# tin_of_fets.net
KiCad netlist of a schematic drawn in EAGLE
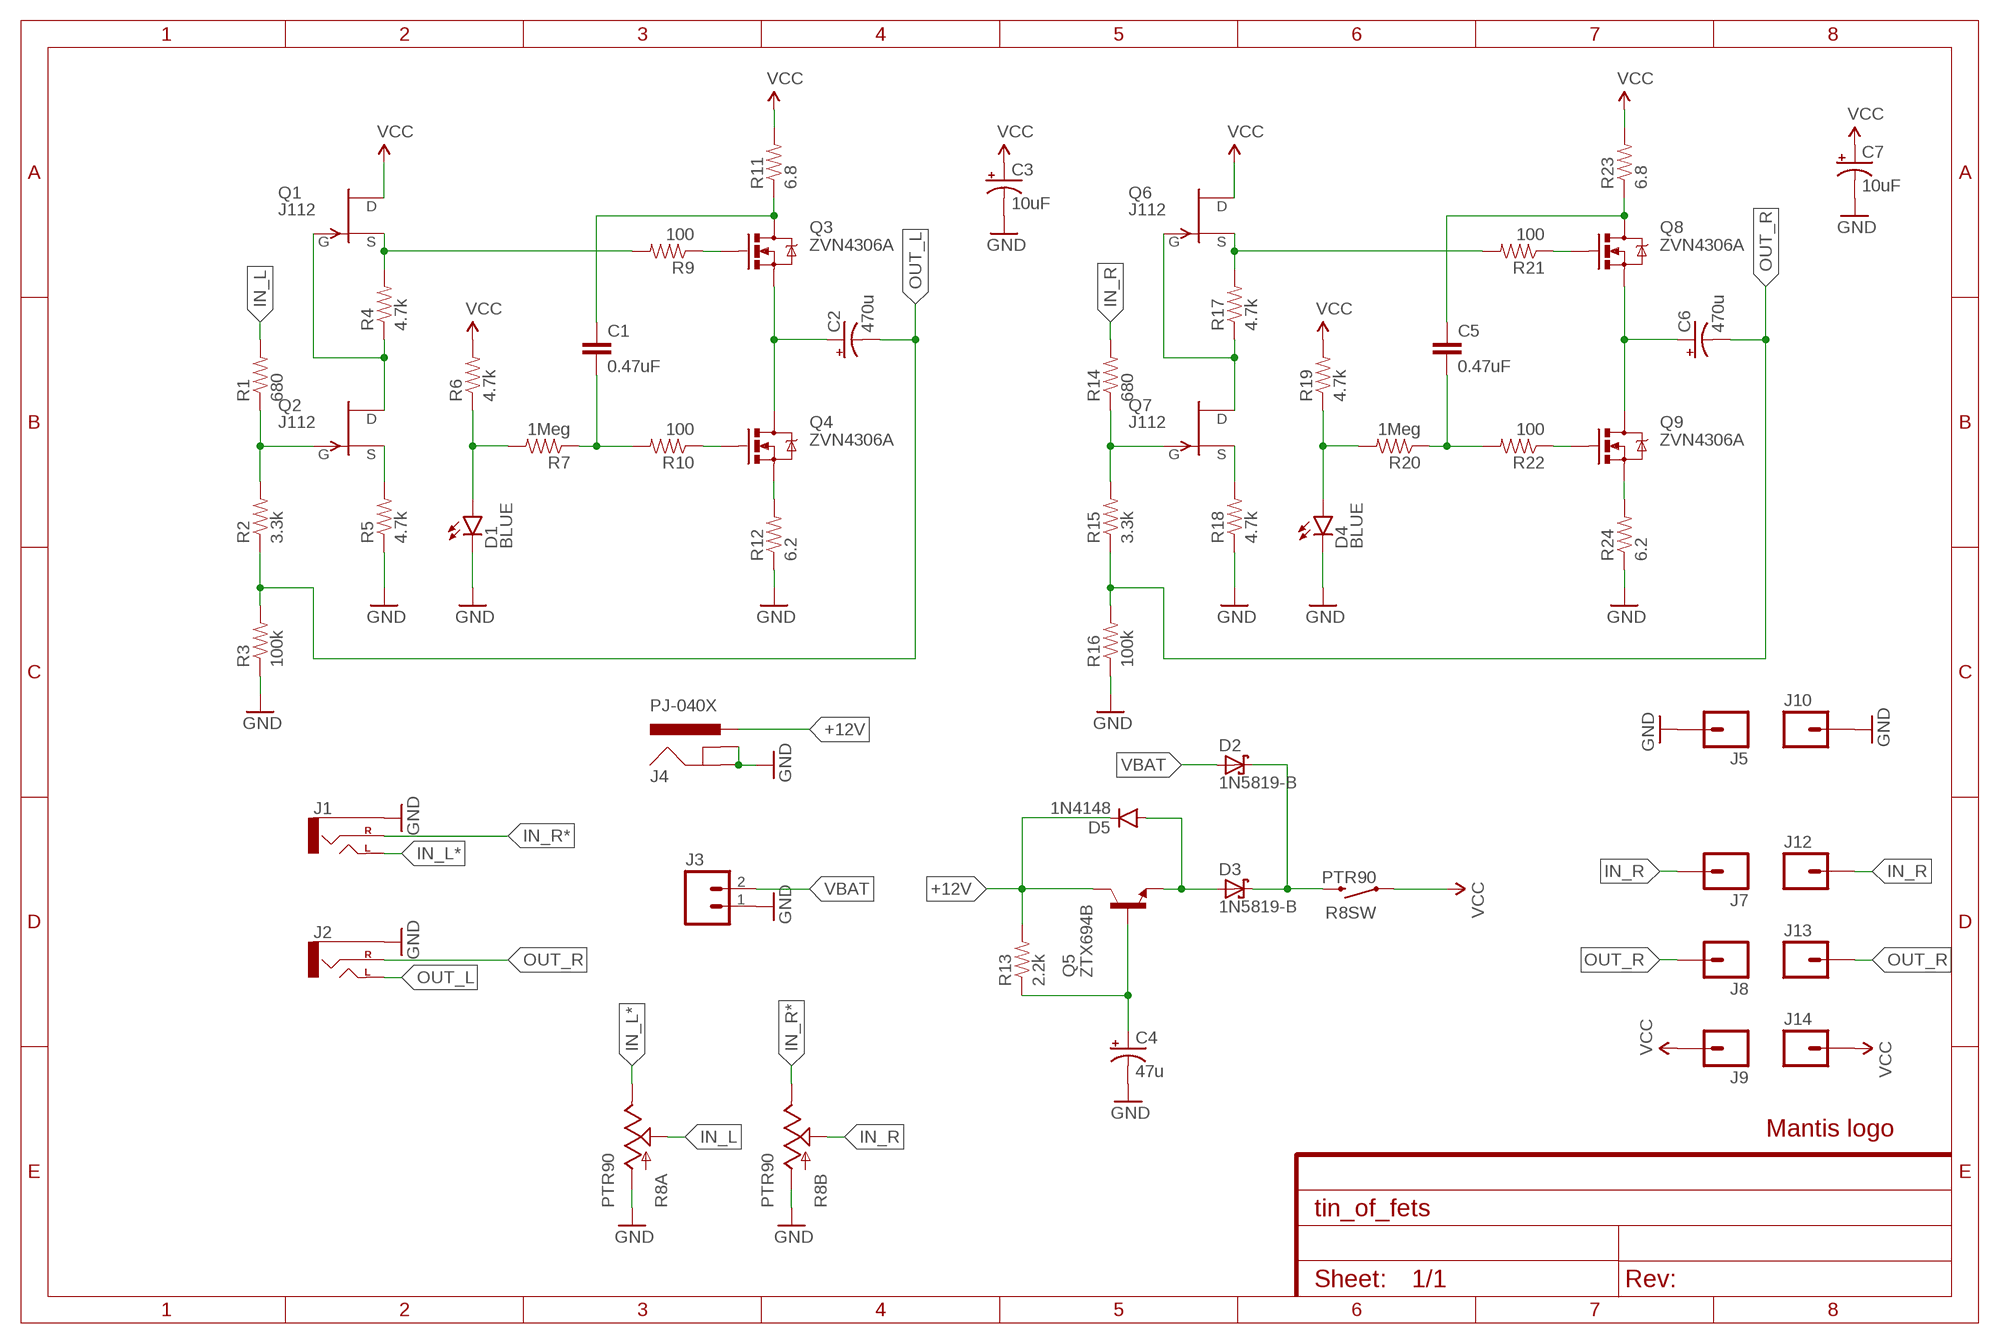
[diagram p0: schematic, sheet 1]

(export (version "E")
  (design (tool "Eeschema 10.0.6"))
  (components
    (comp (ref "C1")
      (value "0.47uF")
      (footprint "eagle-import:C5B3.5")
      (libsource (lib "eagle-import") (part "C5/3.5"))
    )
    (comp (ref "C2")
      (value "470u")
      (footprint "eagle-import:CPOL-RADIAL-8_3.5")
      (libsource (lib "eagle-import") (part "CAP_POLPTH8MM"))
    )
    (comp (ref "C3")
      (value "10uF")
      (footprint "eagle-import:CPOL-RADIAL-10UF-25V-SM")
      (libsource (lib "eagle-import") (part "CAP_POLPTH1-SM"))
    )
    (comp (ref "C4")
      (value "47u")
      (footprint "eagle-import:CPOL-RADIAL-10UF-25V-SM")
      (libsource (lib "eagle-import") (part "CAP_POLPTH1-SM"))
    )
    (comp (ref "C5")
      (value "0.47uF")
      (footprint "eagle-import:C5B3.5")
      (libsource (lib "eagle-import") (part "C5/3.5"))
    )
    (comp (ref "C6")
      (value "470u")
      (footprint "eagle-import:CPOL-RADIAL-8_3.5")
      (libsource (lib "eagle-import") (part "CAP_POLPTH8MM"))
    )
    (comp (ref "C7")
      (value "10uF")
      (footprint "eagle-import:CPOL-RADIAL-10UF-25V-SM")
      (libsource (lib "eagle-import") (part "CAP_POLPTH1-SM"))
    )
    (comp (ref "D1")
      (value "BLUE")
      (footprint "eagle-import:LED3MM-SM")
      (libsource (lib "eagle-import") (part "LED3MM-SM"))
    )
    (comp (ref "D2")
      (value "1N5819-B")
      (footprint "eagle-import:DO41-7.6")
      (libsource (lib "eagle-import") (part "1N5819-B"))
    )
    (comp (ref "D3")
      (value "1N5819-B")
      (footprint "eagle-import:DO41-7.6")
      (libsource (lib "eagle-import") (part "1N5819-B"))
    )
    (comp (ref "D4")
      (value "BLUE")
      (footprint "eagle-import:LED3MM-SM")
      (libsource (lib "eagle-import") (part "LED3MM-SM"))
    )
    (comp (ref "D5")
      (value "1N4148")
      (footprint "eagle-import:DIODE-1N4148")
      (libsource (lib "eagle-import") (part "DIODE1N4148"))
    )
    (comp (ref "J1")
      (value "AUDIO-JACKPTH")
      (footprint "eagle-import:AUDIO-JACK")
      (libsource (lib "eagle-import") (part "AUDIO-JACKPTH"))
    )
    (comp (ref "J2")
      (value "AUDIO-JACKPTH")
      (footprint "eagle-import:AUDIO-JACK")
      (libsource (lib "eagle-import") (part "AUDIO-JACKPTH"))
    )
    (comp (ref "J3")
      (value "M02PTH")
      (footprint "eagle-import:1X02")
      (libsource (lib "eagle-import") (part "M02PTH"))
    )
    (comp (ref "J4")
      (value "PJ-040X")
      (footprint "eagle-import:PJ-040X")
      (libsource (lib "eagle-import") (part "PJ-040X"))
    )
    (comp (ref "J5")
      (value "M01PTH")
      (footprint "eagle-import:1X01")
      (libsource (lib "eagle-import") (part "M01PTH"))
    )
    (comp (ref "J7")
      (value "M01PTH")
      (footprint "eagle-import:1X01")
      (libsource (lib "eagle-import") (part "M01PTH"))
    )
    (comp (ref "J8")
      (value "M01PTH")
      (footprint "eagle-import:1X01")
      (libsource (lib "eagle-import") (part "M01PTH"))
    )
    (comp (ref "J9")
      (value "M01PTH")
      (footprint "eagle-import:1X01")
      (libsource (lib "eagle-import") (part "M01PTH"))
    )
    (comp (ref "J10")
      (value "M01PTH")
      (footprint "eagle-import:1X01")
      (libsource (lib "eagle-import") (part "M01PTH"))
    )
    (comp (ref "J12")
      (value "M01PTH")
      (footprint "eagle-import:1X01")
      (libsource (lib "eagle-import") (part "M01PTH"))
    )
    (comp (ref "J13")
      (value "M01PTH")
      (footprint "eagle-import:1X01")
      (libsource (lib "eagle-import") (part "M01PTH"))
    )
    (comp (ref "J14")
      (value "M01PTH")
      (footprint "eagle-import:1X01")
      (libsource (lib "eagle-import") (part "M01PTH"))
    )
    (comp (ref "LOGO1")
      (value "LOGO-MANTIS")
      (footprint "eagle-import:LOGO-MANTIS")
      (libsource (lib "eagle-import") (part "LOGO-MANTIS"))
    )
    (comp (ref "Q1")
      (value "J112")
      (footprint "eagle-import:TO-92")
      (libsource (lib "eagle-import") (part "J112"))
    )
    (comp (ref "Q2")
      (value "J112")
      (footprint "eagle-import:TO-92")
      (libsource (lib "eagle-import") (part "J112"))
    )
    (comp (ref "Q3")
      (value "ZVN4306A")
      (footprint "eagle-import:TO-92")
      (libsource (lib "eagle-import") (part "ZVN4306A"))
    )
    (comp (ref "Q4")
      (value "ZVN4306A")
      (footprint "eagle-import:TO-92")
      (libsource (lib "eagle-import") (part "ZVN4306A"))
    )
    (comp (ref "Q5")
      (value "ZTX694B")
      (footprint "eagle-import:TO-92")
      (libsource (lib "eagle-import") (part "ZTX694B"))
    )
    (comp (ref "Q6")
      (value "J112")
      (footprint "eagle-import:TO-92")
      (libsource (lib "eagle-import") (part "J112"))
    )
    (comp (ref "Q7")
      (value "J112")
      (footprint "eagle-import:TO-92")
      (libsource (lib "eagle-import") (part "J112"))
    )
    (comp (ref "Q8")
      (value "ZVN4306A")
      (footprint "eagle-import:TO-92")
      (libsource (lib "eagle-import") (part "ZVN4306A"))
    )
    (comp (ref "Q9")
      (value "ZVN4306A")
      (footprint "eagle-import:TO-92")
      (libsource (lib "eagle-import") (part "ZVN4306A"))
    )
    (comp (ref "R1")
      (value "680")
      (footprint "eagle-import:AXIAL-0.4-SM")
      (libsource (lib "eagle-import") (part "RESISTORPTH-1/4W-SM"))
    )
    (comp (ref "R2")
      (value "3.3k")
      (footprint "eagle-import:AXIAL-0.4-SM")
      (libsource (lib "eagle-import") (part "RESISTORPTH-1/4W-SM"))
    )
    (comp (ref "R3")
      (value "100k")
      (footprint "eagle-import:AXIAL-0.4-SM")
      (libsource (lib "eagle-import") (part "RESISTORPTH-1/4W-SM"))
    )
    (comp (ref "R4")
      (value "4.7k")
      (footprint "eagle-import:AXIAL-0.4-SM")
      (libsource (lib "eagle-import") (part "RESISTORPTH-1/4W-SM"))
    )
    (comp (ref "R5")
      (value "4.7k")
      (footprint "eagle-import:AXIAL-0.4-SM")
      (libsource (lib "eagle-import") (part "RESISTORPTH-1/4W-SM"))
    )
    (comp (ref "R6")
      (value "4.7k")
      (footprint "eagle-import:AXIAL-0.4-SM")
      (libsource (lib "eagle-import") (part "RESISTORPTH-1/4W-SM"))
    )
    (comp (ref "R7")
      (value "1Meg")
      (footprint "eagle-import:AXIAL-0.4-SM")
      (libsource (lib "eagle-import") (part "RESISTORPTH-1/4W-SM"))
    )
    (comp (ref "R8")
      (value "PTR90")
      (footprint "eagle-import:PTR902")
      (libsource (lib "eagle-import") (part "PTR90"))
    )
    (comp (ref "R9")
      (value "100")
      (footprint "eagle-import:AXIAL-0.4-SM")
      (libsource (lib "eagle-import") (part "RESISTORPTH-1/4W-SM"))
    )
    (comp (ref "R10")
      (value "100")
      (footprint "eagle-import:AXIAL-0.4-SM")
      (libsource (lib "eagle-import") (part "RESISTORPTH-1/4W-SM"))
    )
    (comp (ref "R11")
      (value "6.8")
      (footprint "eagle-import:AXIAL-0.4-SM")
      (libsource (lib "eagle-import") (part "RESISTORPTH-1/4W-SM"))
    )
    (comp (ref "R12")
      (value "6.2")
      (footprint "eagle-import:AXIAL-0.4-SM")
      (libsource (lib "eagle-import") (part "RESISTORPTH-1/4W-SM"))
    )
    (comp (ref "R13")
      (value "2.2k")
      (footprint "eagle-import:AXIAL-0.4-SM")
      (libsource (lib "eagle-import") (part "RESISTORPTH-1/4W-SM"))
    )
    (comp (ref "R14")
      (value "680")
      (footprint "eagle-import:AXIAL-0.4-SM")
      (libsource (lib "eagle-import") (part "RESISTORPTH-1/4W-SM"))
    )
    (comp (ref "R15")
      (value "3.3k")
      (footprint "eagle-import:AXIAL-0.4-SM")
      (libsource (lib "eagle-import") (part "RESISTORPTH-1/4W-SM"))
    )
    (comp (ref "R16")
      (value "100k")
      (footprint "eagle-import:AXIAL-0.4-SM")
      (libsource (lib "eagle-import") (part "RESISTORPTH-1/4W-SM"))
    )
    (comp (ref "R17")
      (value "4.7k")
      (footprint "eagle-import:AXIAL-0.4-SM")
      (libsource (lib "eagle-import") (part "RESISTORPTH-1/4W-SM"))
    )
    (comp (ref "R18")
      (value "4.7k")
      (footprint "eagle-import:AXIAL-0.4-SM")
      (libsource (lib "eagle-import") (part "RESISTORPTH-1/4W-SM"))
    )
    (comp (ref "R19")
      (value "4.7k")
      (footprint "eagle-import:AXIAL-0.4-SM")
      (libsource (lib "eagle-import") (part "RESISTORPTH-1/4W-SM"))
    )
    (comp (ref "R20")
      (value "1Meg")
      (footprint "eagle-import:AXIAL-0.4-SM")
      (libsource (lib "eagle-import") (part "RESISTORPTH-1/4W-SM"))
    )
    (comp (ref "R21")
      (value "100")
      (footprint "eagle-import:AXIAL-0.4-SM")
      (libsource (lib "eagle-import") (part "RESISTORPTH-1/4W-SM"))
    )
    (comp (ref "R22")
      (value "100")
      (footprint "eagle-import:AXIAL-0.4-SM")
      (libsource (lib "eagle-import") (part "RESISTORPTH-1/4W-SM"))
    )
    (comp (ref "R23")
      (value "6.8")
      (footprint "eagle-import:AXIAL-0.4-SM")
      (libsource (lib "eagle-import") (part "RESISTORPTH-1/4W-SM"))
    )
    (comp (ref "R24")
      (value "6.2")
      (footprint "eagle-import:AXIAL-0.4-SM")
      (libsource (lib "eagle-import") (part "RESISTORPTH-1/4W-SM"))
    )
  )
  (nets
    (net (code "1") (name "+12V") (class "Default")
      (node (ref "D5") (pin "C") (pinfunction "C_C") (pintype "passive"))
      (node (ref "J4") (pin "1") (pinfunction "PWR_1") (pintype "bidirectional"))
      (node (ref "Q5") (pin "3") (pinfunction "C_3") (pintype "passive"))
      (node (ref "R13") (pin "P$2") (pinfunction "2_P$2") (pintype "passive"))
    )
    (net (code "2") (name "GND") (class "Default")
      (node (ref "C3") (pin "2") (pinfunction "-_2") (pintype "passive"))
      (node (ref "C4") (pin "2") (pinfunction "-_2") (pintype "passive"))
      (node (ref "C7") (pin "2") (pinfunction "-_2") (pintype "passive"))
      (node (ref "D1") (pin "K") (pinfunction "C_K") (pintype "passive"))
      (node (ref "D4") (pin "K") (pinfunction "C_K") (pintype "passive"))
      (node (ref "J1") (pin "SLEEVE") (pinfunction "SLEEVE_SLEEVE") (pintype "bidirectional"))
      (node (ref "J10") (pin "1") (pinfunction "1_1") (pintype "passive"))
      (node (ref "J2") (pin "SLEEVE") (pinfunction "SLEEVE_SLEEVE") (pintype "bidirectional"))
      (node (ref "J3") (pin "1") (pinfunction "1_1") (pintype "passive"))
      (node (ref "J4") (pin "2") (pinfunction "GND_2") (pintype "bidirectional"))
      (node (ref "J4") (pin "3") (pinfunction "GNDBREAK_3") (pintype "bidirectional"))
      (node (ref "J5") (pin "1") (pinfunction "1_1") (pintype "passive"))
      (node (ref "R12") (pin "P$1") (pinfunction "1_P$1") (pintype "passive"))
      (node (ref "R16") (pin "P$1") (pinfunction "1_P$1") (pintype "passive"))
      (node (ref "R18") (pin "P$1") (pinfunction "1_P$1") (pintype "passive"))
      (node (ref "R24") (pin "P$1") (pinfunction "1_P$1") (pintype "passive"))
      (node (ref "R3") (pin "P$1") (pinfunction "1_P$1") (pintype "passive"))
      (node (ref "R5") (pin "P$1") (pinfunction "1_P$1") (pintype "passive"))
      (node (ref "R8") (pin "R1.1") (pinfunction "A_R1.1") (pintype "passive"))
      (node (ref "R8") (pin "R2.1") (pinfunction "A_R2.1") (pintype "passive"))
    )
    (net (code "3") (name "IN_L") (class "Default")
      (node (ref "R1") (pin "P$2") (pinfunction "2_P$2") (pintype "passive"))
      (node (ref "R8") (pin "R1.2") (pinfunction "S_R1.2") (pintype "passive"))
    )
    (net (code "4") (name "IN_L*") (class "Default")
      (node (ref "J1") (pin "TIP") (pinfunction "LEFT_TIP") (pintype "bidirectional"))
      (node (ref "R8") (pin "R1.3") (pinfunction "E_R1.3") (pintype "passive"))
    )
    (net (code "5") (name "IN_R") (class "Default")
      (node (ref "J12") (pin "1") (pinfunction "1_1") (pintype "passive"))
      (node (ref "J7") (pin "1") (pinfunction "1_1") (pintype "passive"))
      (node (ref "R14") (pin "P$2") (pinfunction "2_P$2") (pintype "passive"))
      (node (ref "R8") (pin "R2.2") (pinfunction "S_R2.2") (pintype "passive"))
    )
    (net (code "6") (name "IN_R*") (class "Default")
      (node (ref "J1") (pin "RING") (pinfunction "RIGHT_RING") (pintype "bidirectional"))
      (node (ref "R8") (pin "R2.3") (pinfunction "E_R2.3") (pintype "passive"))
    )
    (net (code "7") (name "Net-(C2-+)") (class "Default")
      (node (ref "C2") (pin "1") (pinfunction "+_1") (pintype "passive"))
      (node (ref "Q3") (pin "1") (pinfunction "S_1") (pintype "passive"))
      (node (ref "Q4") (pin "3") (pinfunction "D_3") (pintype "passive"))
    )
    (net (code "8") (name "Net-(C4-+)") (class "Default")
      (node (ref "C4") (pin "1") (pinfunction "+_1") (pintype "passive"))
      (node (ref "Q5") (pin "2") (pinfunction "B_2") (pintype "passive"))
      (node (ref "R13") (pin "P$1") (pinfunction "1_P$1") (pintype "passive"))
    )
    (net (code "9") (name "Net-(C6-+)") (class "Default")
      (node (ref "C6") (pin "1") (pinfunction "+_1") (pintype "passive"))
      (node (ref "Q8") (pin "1") (pinfunction "S_1") (pintype "passive"))
      (node (ref "Q9") (pin "3") (pinfunction "D_3") (pintype "passive"))
    )
    (net (code "10") (name "Net-(Q1-G)") (class "Default")
      (node (ref "Q1") (pin "3") (pinfunction "G_3") (pintype "passive"))
      (node (ref "Q2") (pin "1") (pinfunction "D_1") (pintype "passive"))
      (node (ref "R4") (pin "P$1") (pinfunction "1_P$1") (pintype "passive"))
    )
    (net (code "11") (name "Net-(Q1-S)") (class "Default")
      (node (ref "Q1") (pin "2") (pinfunction "S_2") (pintype "passive"))
      (node (ref "R4") (pin "P$2") (pinfunction "2_P$2") (pintype "passive"))
      (node (ref "R9") (pin "P$2") (pinfunction "2_P$2") (pintype "passive"))
    )
    (net (code "12") (name "Net-(Q2-G)") (class "Default")
      (node (ref "Q2") (pin "3") (pinfunction "G_3") (pintype "passive"))
      (node (ref "R1") (pin "P$1") (pinfunction "1_P$1") (pintype "passive"))
      (node (ref "R2") (pin "P$2") (pinfunction "2_P$2") (pintype "passive"))
    )
    (net (code "13") (name "Net-(Q2-S)") (class "Default")
      (node (ref "Q2") (pin "2") (pinfunction "S_2") (pintype "passive"))
      (node (ref "R5") (pin "P$2") (pinfunction "2_P$2") (pintype "passive"))
    )
    (net (code "14") (name "Net-(Q3-D)") (class "Default")
      (node (ref "C1") (pin "1") (pinfunction "1_1") (pintype "passive"))
      (node (ref "Q3") (pin "3") (pinfunction "D_3") (pintype "passive"))
      (node (ref "R11") (pin "P$1") (pinfunction "1_P$1") (pintype "passive"))
    )
    (net (code "15") (name "Net-(Q3-G)") (class "Default")
      (node (ref "Q3") (pin "2") (pinfunction "G_2") (pintype "passive"))
      (node (ref "R9") (pin "P$1") (pinfunction "1_P$1") (pintype "passive"))
    )
    (net (code "16") (name "Net-(Q4-G)") (class "Default")
      (node (ref "Q4") (pin "2") (pinfunction "G_2") (pintype "passive"))
      (node (ref "R10") (pin "P$1") (pinfunction "1_P$1") (pintype "passive"))
    )
    (net (code "17") (name "Net-(Q4-S)") (class "Default")
      (node (ref "Q4") (pin "1") (pinfunction "S_1") (pintype "passive"))
      (node (ref "R12") (pin "P$2") (pinfunction "2_P$2") (pintype "passive"))
    )
    (net (code "18") (name "Net-(Q5-E)") (class "Default")
      (node (ref "D3") (pin "A") (pinfunction "A_A") (pintype "passive"))
      (node (ref "D5") (pin "A") (pinfunction "A_A") (pintype "passive"))
      (node (ref "Q5") (pin "1") (pinfunction "E_1") (pintype "passive"))
    )
    (net (code "19") (name "Net-(Q6-G)") (class "Default")
      (node (ref "Q6") (pin "3") (pinfunction "G_3") (pintype "passive"))
      (node (ref "Q7") (pin "1") (pinfunction "D_1") (pintype "passive"))
      (node (ref "R17") (pin "P$1") (pinfunction "1_P$1") (pintype "passive"))
    )
    (net (code "20") (name "Net-(Q6-S)") (class "Default")
      (node (ref "Q6") (pin "2") (pinfunction "S_2") (pintype "passive"))
      (node (ref "R17") (pin "P$2") (pinfunction "2_P$2") (pintype "passive"))
      (node (ref "R21") (pin "P$2") (pinfunction "2_P$2") (pintype "passive"))
    )
    (net (code "21") (name "Net-(Q7-G)") (class "Default")
      (node (ref "Q7") (pin "3") (pinfunction "G_3") (pintype "passive"))
      (node (ref "R14") (pin "P$1") (pinfunction "1_P$1") (pintype "passive"))
      (node (ref "R15") (pin "P$2") (pinfunction "2_P$2") (pintype "passive"))
    )
    (net (code "22") (name "Net-(Q7-S)") (class "Default")
      (node (ref "Q7") (pin "2") (pinfunction "S_2") (pintype "passive"))
      (node (ref "R18") (pin "P$2") (pinfunction "2_P$2") (pintype "passive"))
    )
    (net (code "23") (name "Net-(Q8-D)") (class "Default")
      (node (ref "C5") (pin "1") (pinfunction "1_1") (pintype "passive"))
      (node (ref "Q8") (pin "3") (pinfunction "D_3") (pintype "passive"))
      (node (ref "R23") (pin "P$1") (pinfunction "1_P$1") (pintype "passive"))
    )
    (net (code "24") (name "Net-(Q8-G)") (class "Default")
      (node (ref "Q8") (pin "2") (pinfunction "G_2") (pintype "passive"))
      (node (ref "R21") (pin "P$1") (pinfunction "1_P$1") (pintype "passive"))
    )
    (net (code "25") (name "Net-(Q9-G)") (class "Default")
      (node (ref "Q9") (pin "2") (pinfunction "G_2") (pintype "passive"))
      (node (ref "R22") (pin "P$1") (pinfunction "1_P$1") (pintype "passive"))
    )
    (net (code "26") (name "Net-(Q9-S)") (class "Default")
      (node (ref "Q9") (pin "1") (pinfunction "S_1") (pintype "passive"))
      (node (ref "R24") (pin "P$2") (pinfunction "2_P$2") (pintype "passive"))
    )
    (net (code "27") (name "Net-(R6-1)") (class "Default")
      (node (ref "D1") (pin "A") (pinfunction "A_A") (pintype "passive"))
      (node (ref "R6") (pin "P$1") (pinfunction "1_P$1") (pintype "passive"))
      (node (ref "R7") (pin "P$2") (pinfunction "2_P$2") (pintype "passive"))
    )
    (net (code "28") (name "Net-(R8C-2)") (class "Default")
      (node (ref "D2") (pin "C") (pinfunction "C_C") (pintype "passive"))
      (node (ref "D3") (pin "C") (pinfunction "C_C") (pintype "passive"))
      (node (ref "R8") (pin "SW2") (pinfunction "2_SW2") (pintype "passive"))
    )
    (net (code "29") (name "Net-(R10-2)") (class "Default")
      (node (ref "C1") (pin "2") (pinfunction "2_2") (pintype "passive"))
      (node (ref "R10") (pin "P$2") (pinfunction "2_P$2") (pintype "passive"))
      (node (ref "R7") (pin "P$1") (pinfunction "1_P$1") (pintype "passive"))
    )
    (net (code "30") (name "Net-(R19-1)") (class "Default")
      (node (ref "D4") (pin "A") (pinfunction "A_A") (pintype "passive"))
      (node (ref "R19") (pin "P$1") (pinfunction "1_P$1") (pintype "passive"))
      (node (ref "R20") (pin "P$2") (pinfunction "2_P$2") (pintype "passive"))
    )
    (net (code "31") (name "Net-(R20-1)") (class "Default")
      (node (ref "C5") (pin "2") (pinfunction "2_2") (pintype "passive"))
      (node (ref "R20") (pin "P$1") (pinfunction "1_P$1") (pintype "passive"))
      (node (ref "R22") (pin "P$2") (pinfunction "2_P$2") (pintype "passive"))
    )
    (net (code "32") (name "OUT_L") (class "Default")
      (node (ref "C2") (pin "2") (pinfunction "-_2") (pintype "passive"))
      (node (ref "J2") (pin "TIP") (pinfunction "LEFT_TIP") (pintype "bidirectional"))
      (node (ref "R2") (pin "P$1") (pinfunction "1_P$1") (pintype "passive"))
      (node (ref "R3") (pin "P$2") (pinfunction "2_P$2") (pintype "passive"))
    )
    (net (code "33") (name "OUT_R") (class "Default")
      (node (ref "C6") (pin "2") (pinfunction "-_2") (pintype "passive"))
      (node (ref "J13") (pin "1") (pinfunction "1_1") (pintype "passive"))
      (node (ref "J2") (pin "RING") (pinfunction "RIGHT_RING") (pintype "bidirectional"))
      (node (ref "J8") (pin "1") (pinfunction "1_1") (pintype "passive"))
      (node (ref "R15") (pin "P$1") (pinfunction "1_P$1") (pintype "passive"))
      (node (ref "R16") (pin "P$2") (pinfunction "2_P$2") (pintype "passive"))
    )
    (net (code "34") (name "VBAT") (class "Default")
      (node (ref "D2") (pin "A") (pinfunction "A_A") (pintype "passive"))
      (node (ref "J3") (pin "2") (pinfunction "2_2") (pintype "passive"))
    )
    (net (code "35") (name "VCC") (class "Default")
      (node (ref "C3") (pin "1") (pinfunction "+_1") (pintype "passive"))
      (node (ref "C7") (pin "1") (pinfunction "+_1") (pintype "passive"))
      (node (ref "J14") (pin "1") (pinfunction "1_1") (pintype "passive"))
      (node (ref "J9") (pin "1") (pinfunction "1_1") (pintype "passive"))
      (node (ref "Q1") (pin "1") (pinfunction "D_1") (pintype "passive"))
      (node (ref "Q6") (pin "1") (pinfunction "D_1") (pintype "passive"))
      (node (ref "R11") (pin "P$2") (pinfunction "2_P$2") (pintype "passive"))
      (node (ref "R19") (pin "P$2") (pinfunction "2_P$2") (pintype "passive"))
      (node (ref "R23") (pin "P$2") (pinfunction "2_P$2") (pintype "passive"))
      (node (ref "R6") (pin "P$2") (pinfunction "2_P$2") (pintype "passive"))
      (node (ref "R8") (pin "SW1") (pinfunction "1_SW1") (pintype "passive"))
    )
  )
)
